# 3x3_test.net
KiCad netlist of a schematic drawn in EAGLE
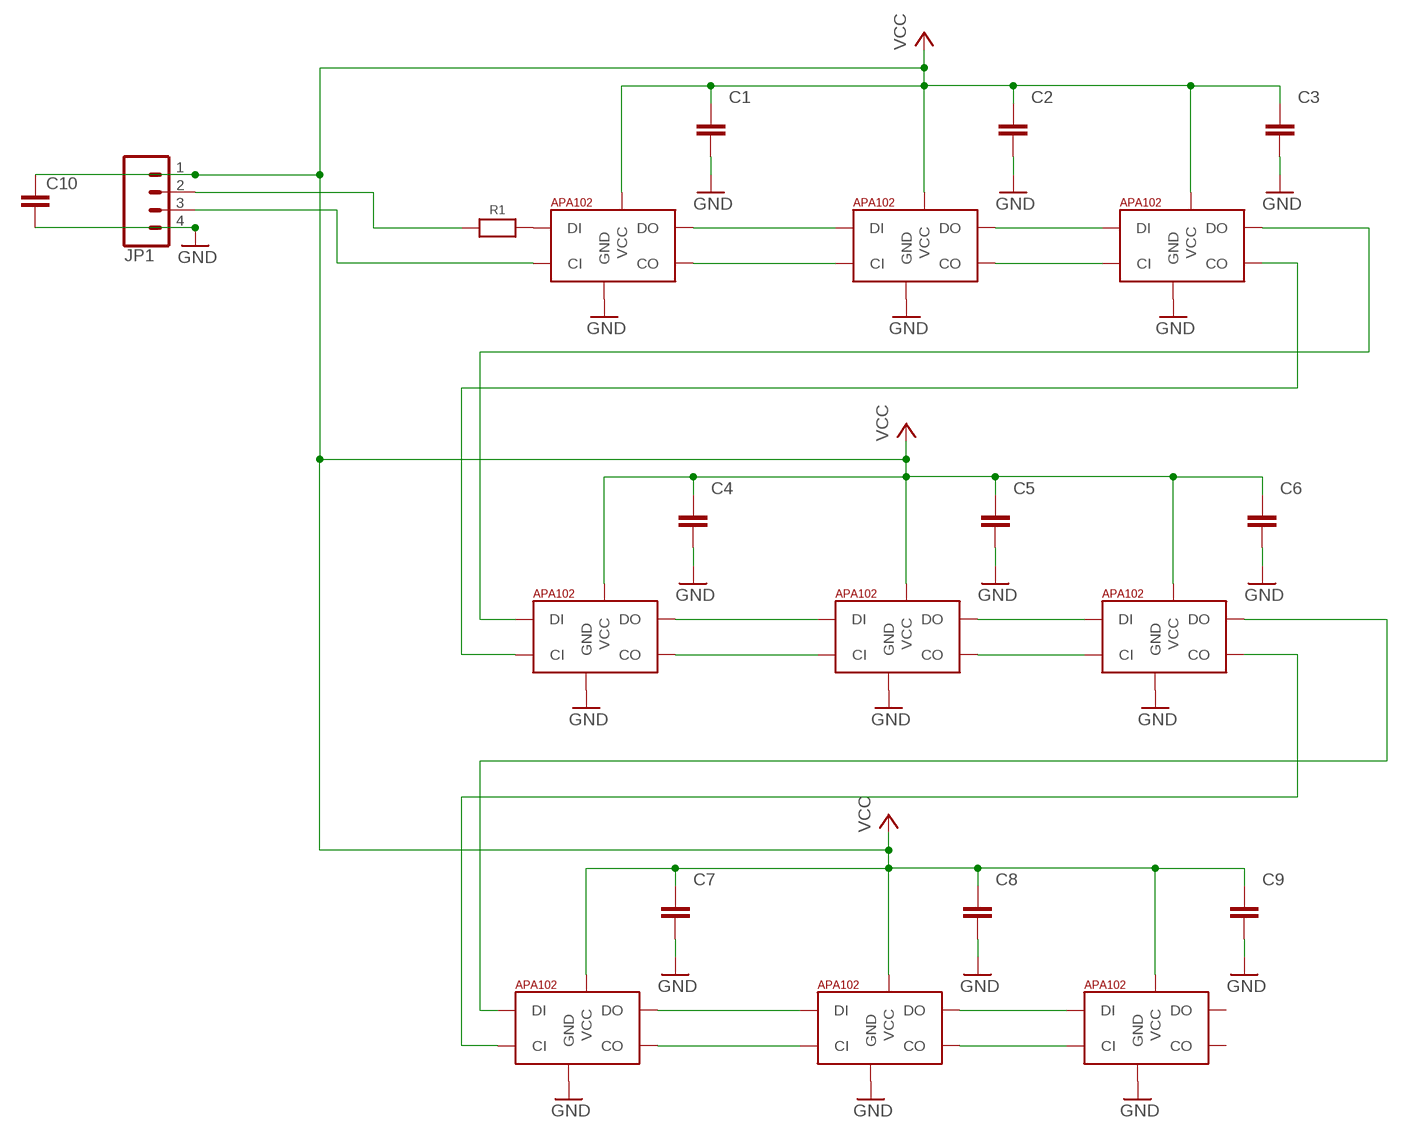
[diagram p0: schematic, sheet 1]

(export (version "E")
  (design (tool "Eeschema 10.0.6"))
  (components
    (comp (ref "C1")
      (value "CAPACITOR_NPOL-0805")
      (footprint "eagle-import:C805")
      (libsource (lib "eagle-import") (part "CAPACITOR_NPOL-0805"))
    )
    (comp (ref "C2")
      (value "CAPACITOR_NPOL-0805")
      (footprint "eagle-import:C805")
      (libsource (lib "eagle-import") (part "CAPACITOR_NPOL-0805"))
    )
    (comp (ref "C3")
      (value "CAPACITOR_NPOL-0805")
      (footprint "eagle-import:C805")
      (libsource (lib "eagle-import") (part "CAPACITOR_NPOL-0805"))
    )
    (comp (ref "C4")
      (value "CAPACITOR_NPOL-0805")
      (footprint "eagle-import:C805")
      (libsource (lib "eagle-import") (part "CAPACITOR_NPOL-0805"))
    )
    (comp (ref "C5")
      (value "CAPACITOR_NPOL-0805")
      (footprint "eagle-import:C805")
      (libsource (lib "eagle-import") (part "CAPACITOR_NPOL-0805"))
    )
    (comp (ref "C6")
      (value "CAPACITOR_NPOL-0805")
      (footprint "eagle-import:C805")
      (libsource (lib "eagle-import") (part "CAPACITOR_NPOL-0805"))
    )
    (comp (ref "C7")
      (value "CAPACITOR_NPOL-0805")
      (footprint "eagle-import:C805")
      (libsource (lib "eagle-import") (part "CAPACITOR_NPOL-0805"))
    )
    (comp (ref "C8")
      (value "CAPACITOR_NPOL-0805")
      (footprint "eagle-import:C805")
      (libsource (lib "eagle-import") (part "CAPACITOR_NPOL-0805"))
    )
    (comp (ref "C9")
      (value "CAPACITOR_NPOL-0805")
      (footprint "eagle-import:C805")
      (libsource (lib "eagle-import") (part "CAPACITOR_NPOL-0805"))
    )
    (comp (ref "C10")
      (value "C-EUC0805")
      (footprint "eagle-import:C0805")
      (libsource (lib "eagle-import") (part "C-EUC0805"))
    )
    (comp (ref "JP1")
      (value "CONN_04")
      (footprint "eagle-import:1X04")
      (libsource (lib "eagle-import") (part "CONN_04"))
    )
    (comp (ref "R1")
      (value "RESISTOR0805_NOOUTLINE")
      (footprint "eagle-import:0805-NO")
      (libsource (lib "eagle-import") (part "RESISTOR0805_NOOUTLINE"))
    )
    (comp (ref "U$1")
      (value "APA1025050")
      (footprint "eagle-import:APA102_5050")
      (libsource (lib "eagle-import") (part "APA1025050"))
    )
    (comp (ref "U$2")
      (value "APA1025050")
      (footprint "eagle-import:APA102_5050")
      (libsource (lib "eagle-import") (part "APA1025050"))
    )
    (comp (ref "U$3")
      (value "APA1025050")
      (footprint "eagle-import:APA102_5050")
      (libsource (lib "eagle-import") (part "APA1025050"))
    )
    (comp (ref "U$4")
      (value "APA1025050")
      (footprint "eagle-import:APA102_5050")
      (libsource (lib "eagle-import") (part "APA1025050"))
    )
    (comp (ref "U$5")
      (value "APA1025050")
      (footprint "eagle-import:APA102_5050")
      (libsource (lib "eagle-import") (part "APA1025050"))
    )
    (comp (ref "U$6")
      (value "APA1025050")
      (footprint "eagle-import:APA102_5050")
      (libsource (lib "eagle-import") (part "APA1025050"))
    )
    (comp (ref "U$7")
      (value "APA1025050")
      (footprint "eagle-import:APA102_5050")
      (libsource (lib "eagle-import") (part "APA1025050"))
    )
    (comp (ref "U$8")
      (value "APA1025050")
      (footprint "eagle-import:APA102_5050")
      (libsource (lib "eagle-import") (part "APA1025050"))
    )
    (comp (ref "U$9")
      (value "APA1025050")
      (footprint "eagle-import:APA102_5050")
      (libsource (lib "eagle-import") (part "APA1025050"))
    )
  )
  (nets
    (net (code "1") (name "GND") (class "Default")
      (node (ref "C1") (pin "2") (pinfunction "2_2") (pintype "passive"))
      (node (ref "C10") (pin "2") (pinfunction "2_2") (pintype "passive"))
      (node (ref "C2") (pin "2") (pinfunction "2_2") (pintype "passive"))
      (node (ref "C3") (pin "2") (pinfunction "2_2") (pintype "passive"))
      (node (ref "C4") (pin "2") (pinfunction "2_2") (pintype "passive"))
      (node (ref "C5") (pin "2") (pinfunction "2_2") (pintype "passive"))
      (node (ref "C6") (pin "2") (pinfunction "2_2") (pintype "passive"))
      (node (ref "C7") (pin "2") (pinfunction "2_2") (pintype "passive"))
      (node (ref "C8") (pin "2") (pinfunction "2_2") (pintype "passive"))
      (node (ref "C9") (pin "2") (pinfunction "2_2") (pintype "passive"))
      (node (ref "JP1") (pin "4") (pinfunction "4_4") (pintype "passive"))
      (node (ref "U$1") (pin "6") (pinfunction "GND_6") (pintype "bidirectional"))
      (node (ref "U$2") (pin "6") (pinfunction "GND_6") (pintype "bidirectional"))
      (node (ref "U$3") (pin "6") (pinfunction "GND_6") (pintype "bidirectional"))
      (node (ref "U$4") (pin "6") (pinfunction "GND_6") (pintype "bidirectional"))
      (node (ref "U$5") (pin "6") (pinfunction "GND_6") (pintype "bidirectional"))
      (node (ref "U$6") (pin "6") (pinfunction "GND_6") (pintype "bidirectional"))
      (node (ref "U$7") (pin "6") (pinfunction "GND_6") (pintype "bidirectional"))
      (node (ref "U$8") (pin "6") (pinfunction "GND_6") (pintype "bidirectional"))
      (node (ref "U$9") (pin "6") (pinfunction "GND_6") (pintype "bidirectional"))
    )
    (net (code "2") (name "Net-(JP1-Pad2)") (class "Default")
      (node (ref "JP1") (pin "2") (pinfunction "2_2") (pintype "passive"))
      (node (ref "R1") (pin "1") (pinfunction "1_1") (pintype "passive"))
    )
    (net (code "3") (name "Net-(U$1-CI)") (class "Default")
      (node (ref "JP1") (pin "3") (pinfunction "3_3") (pintype "passive"))
      (node (ref "U$1") (pin "5") (pinfunction "CI_5") (pintype "bidirectional"))
    )
    (net (code "4") (name "Net-(U$1-CO)") (class "Default")
      (node (ref "U$1") (pin "2") (pinfunction "CO_2") (pintype "bidirectional"))
      (node (ref "U$2") (pin "5") (pinfunction "CI_5") (pintype "bidirectional"))
    )
    (net (code "5") (name "Net-(U$1-DI)") (class "Default")
      (node (ref "R1") (pin "2") (pinfunction "2_2") (pintype "passive"))
      (node (ref "U$1") (pin "4") (pinfunction "DI_4") (pintype "bidirectional"))
    )
    (net (code "6") (name "Net-(U$1-DO)") (class "Default")
      (node (ref "U$1") (pin "3") (pinfunction "DO_3") (pintype "bidirectional"))
      (node (ref "U$2") (pin "4") (pinfunction "DI_4") (pintype "bidirectional"))
    )
    (net (code "7") (name "Net-(U$2-CO)") (class "Default")
      (node (ref "U$2") (pin "2") (pinfunction "CO_2") (pintype "bidirectional"))
      (node (ref "U$3") (pin "5") (pinfunction "CI_5") (pintype "bidirectional"))
    )
    (net (code "8") (name "Net-(U$2-DO)") (class "Default")
      (node (ref "U$2") (pin "3") (pinfunction "DO_3") (pintype "bidirectional"))
      (node (ref "U$3") (pin "4") (pinfunction "DI_4") (pintype "bidirectional"))
    )
    (net (code "9") (name "Net-(U$3-CO)") (class "Default")
      (node (ref "U$3") (pin "2") (pinfunction "CO_2") (pintype "bidirectional"))
      (node (ref "U$4") (pin "5") (pinfunction "CI_5") (pintype "bidirectional"))
    )
    (net (code "10") (name "Net-(U$3-DO)") (class "Default")
      (node (ref "U$3") (pin "3") (pinfunction "DO_3") (pintype "bidirectional"))
      (node (ref "U$4") (pin "4") (pinfunction "DI_4") (pintype "bidirectional"))
    )
    (net (code "11") (name "Net-(U$4-CO)") (class "Default")
      (node (ref "U$4") (pin "2") (pinfunction "CO_2") (pintype "bidirectional"))
      (node (ref "U$5") (pin "5") (pinfunction "CI_5") (pintype "bidirectional"))
    )
    (net (code "12") (name "Net-(U$4-DO)") (class "Default")
      (node (ref "U$4") (pin "3") (pinfunction "DO_3") (pintype "bidirectional"))
      (node (ref "U$5") (pin "4") (pinfunction "DI_4") (pintype "bidirectional"))
    )
    (net (code "13") (name "Net-(U$5-CO)") (class "Default")
      (node (ref "U$5") (pin "2") (pinfunction "CO_2") (pintype "bidirectional"))
      (node (ref "U$6") (pin "5") (pinfunction "CI_5") (pintype "bidirectional"))
    )
    (net (code "14") (name "Net-(U$5-DO)") (class "Default")
      (node (ref "U$5") (pin "3") (pinfunction "DO_3") (pintype "bidirectional"))
      (node (ref "U$6") (pin "4") (pinfunction "DI_4") (pintype "bidirectional"))
    )
    (net (code "15") (name "Net-(U$6-CO)") (class "Default")
      (node (ref "U$6") (pin "2") (pinfunction "CO_2") (pintype "bidirectional"))
      (node (ref "U$7") (pin "5") (pinfunction "CI_5") (pintype "bidirectional"))
    )
    (net (code "16") (name "Net-(U$6-DO)") (class "Default")
      (node (ref "U$6") (pin "3") (pinfunction "DO_3") (pintype "bidirectional"))
      (node (ref "U$7") (pin "4") (pinfunction "DI_4") (pintype "bidirectional"))
    )
    (net (code "17") (name "Net-(U$7-CO)") (class "Default")
      (node (ref "U$7") (pin "2") (pinfunction "CO_2") (pintype "bidirectional"))
      (node (ref "U$8") (pin "5") (pinfunction "CI_5") (pintype "bidirectional"))
    )
    (net (code "18") (name "Net-(U$7-DO)") (class "Default")
      (node (ref "U$7") (pin "3") (pinfunction "DO_3") (pintype "bidirectional"))
      (node (ref "U$8") (pin "4") (pinfunction "DI_4") (pintype "bidirectional"))
    )
    (net (code "19") (name "Net-(U$8-CO)") (class "Default")
      (node (ref "U$8") (pin "2") (pinfunction "CO_2") (pintype "bidirectional"))
      (node (ref "U$9") (pin "5") (pinfunction "CI_5") (pintype "bidirectional"))
    )
    (net (code "20") (name "Net-(U$8-DO)") (class "Default")
      (node (ref "U$8") (pin "3") (pinfunction "DO_3") (pintype "bidirectional"))
      (node (ref "U$9") (pin "4") (pinfunction "DI_4") (pintype "bidirectional"))
    )
    (net (code "21") (name "VCC") (class "Default")
      (node (ref "C1") (pin "1") (pinfunction "1_1") (pintype "passive"))
      (node (ref "C10") (pin "1") (pinfunction "1_1") (pintype "passive"))
      (node (ref "C2") (pin "1") (pinfunction "1_1") (pintype "passive"))
      (node (ref "C3") (pin "1") (pinfunction "1_1") (pintype "passive"))
      (node (ref "C4") (pin "1") (pinfunction "1_1") (pintype "passive"))
      (node (ref "C5") (pin "1") (pinfunction "1_1") (pintype "passive"))
      (node (ref "C6") (pin "1") (pinfunction "1_1") (pintype "passive"))
      (node (ref "C7") (pin "1") (pinfunction "1_1") (pintype "passive"))
      (node (ref "C8") (pin "1") (pinfunction "1_1") (pintype "passive"))
      (node (ref "C9") (pin "1") (pinfunction "1_1") (pintype "passive"))
      (node (ref "JP1") (pin "1") (pinfunction "1_1") (pintype "passive"))
      (node (ref "U$1") (pin "1") (pinfunction "VCC_1") (pintype "bidirectional"))
      (node (ref "U$2") (pin "1") (pinfunction "VCC_1") (pintype "bidirectional"))
      (node (ref "U$3") (pin "1") (pinfunction "VCC_1") (pintype "bidirectional"))
      (node (ref "U$4") (pin "1") (pinfunction "VCC_1") (pintype "bidirectional"))
      (node (ref "U$5") (pin "1") (pinfunction "VCC_1") (pintype "bidirectional"))
      (node (ref "U$6") (pin "1") (pinfunction "VCC_1") (pintype "bidirectional"))
      (node (ref "U$7") (pin "1") (pinfunction "VCC_1") (pintype "bidirectional"))
      (node (ref "U$8") (pin "1") (pinfunction "VCC_1") (pintype "bidirectional"))
      (node (ref "U$9") (pin "1") (pinfunction "VCC_1") (pintype "bidirectional"))
    )
    (net (code "22") (name "unconnected-(U$9-CO-Pad2)") (class "Default")
      (node (ref "U$9") (pin "2") (pinfunction "CO_2") (pintype "bidirectional"))
    )
    (net (code "23") (name "unconnected-(U$9-DO-Pad3)") (class "Default")
      (node (ref "U$9") (pin "3") (pinfunction "DO_3") (pintype "bidirectional"))
    )
  )
)
